# Sheet8.net
KiCad netlist of a schematic drawn in Altium Designer
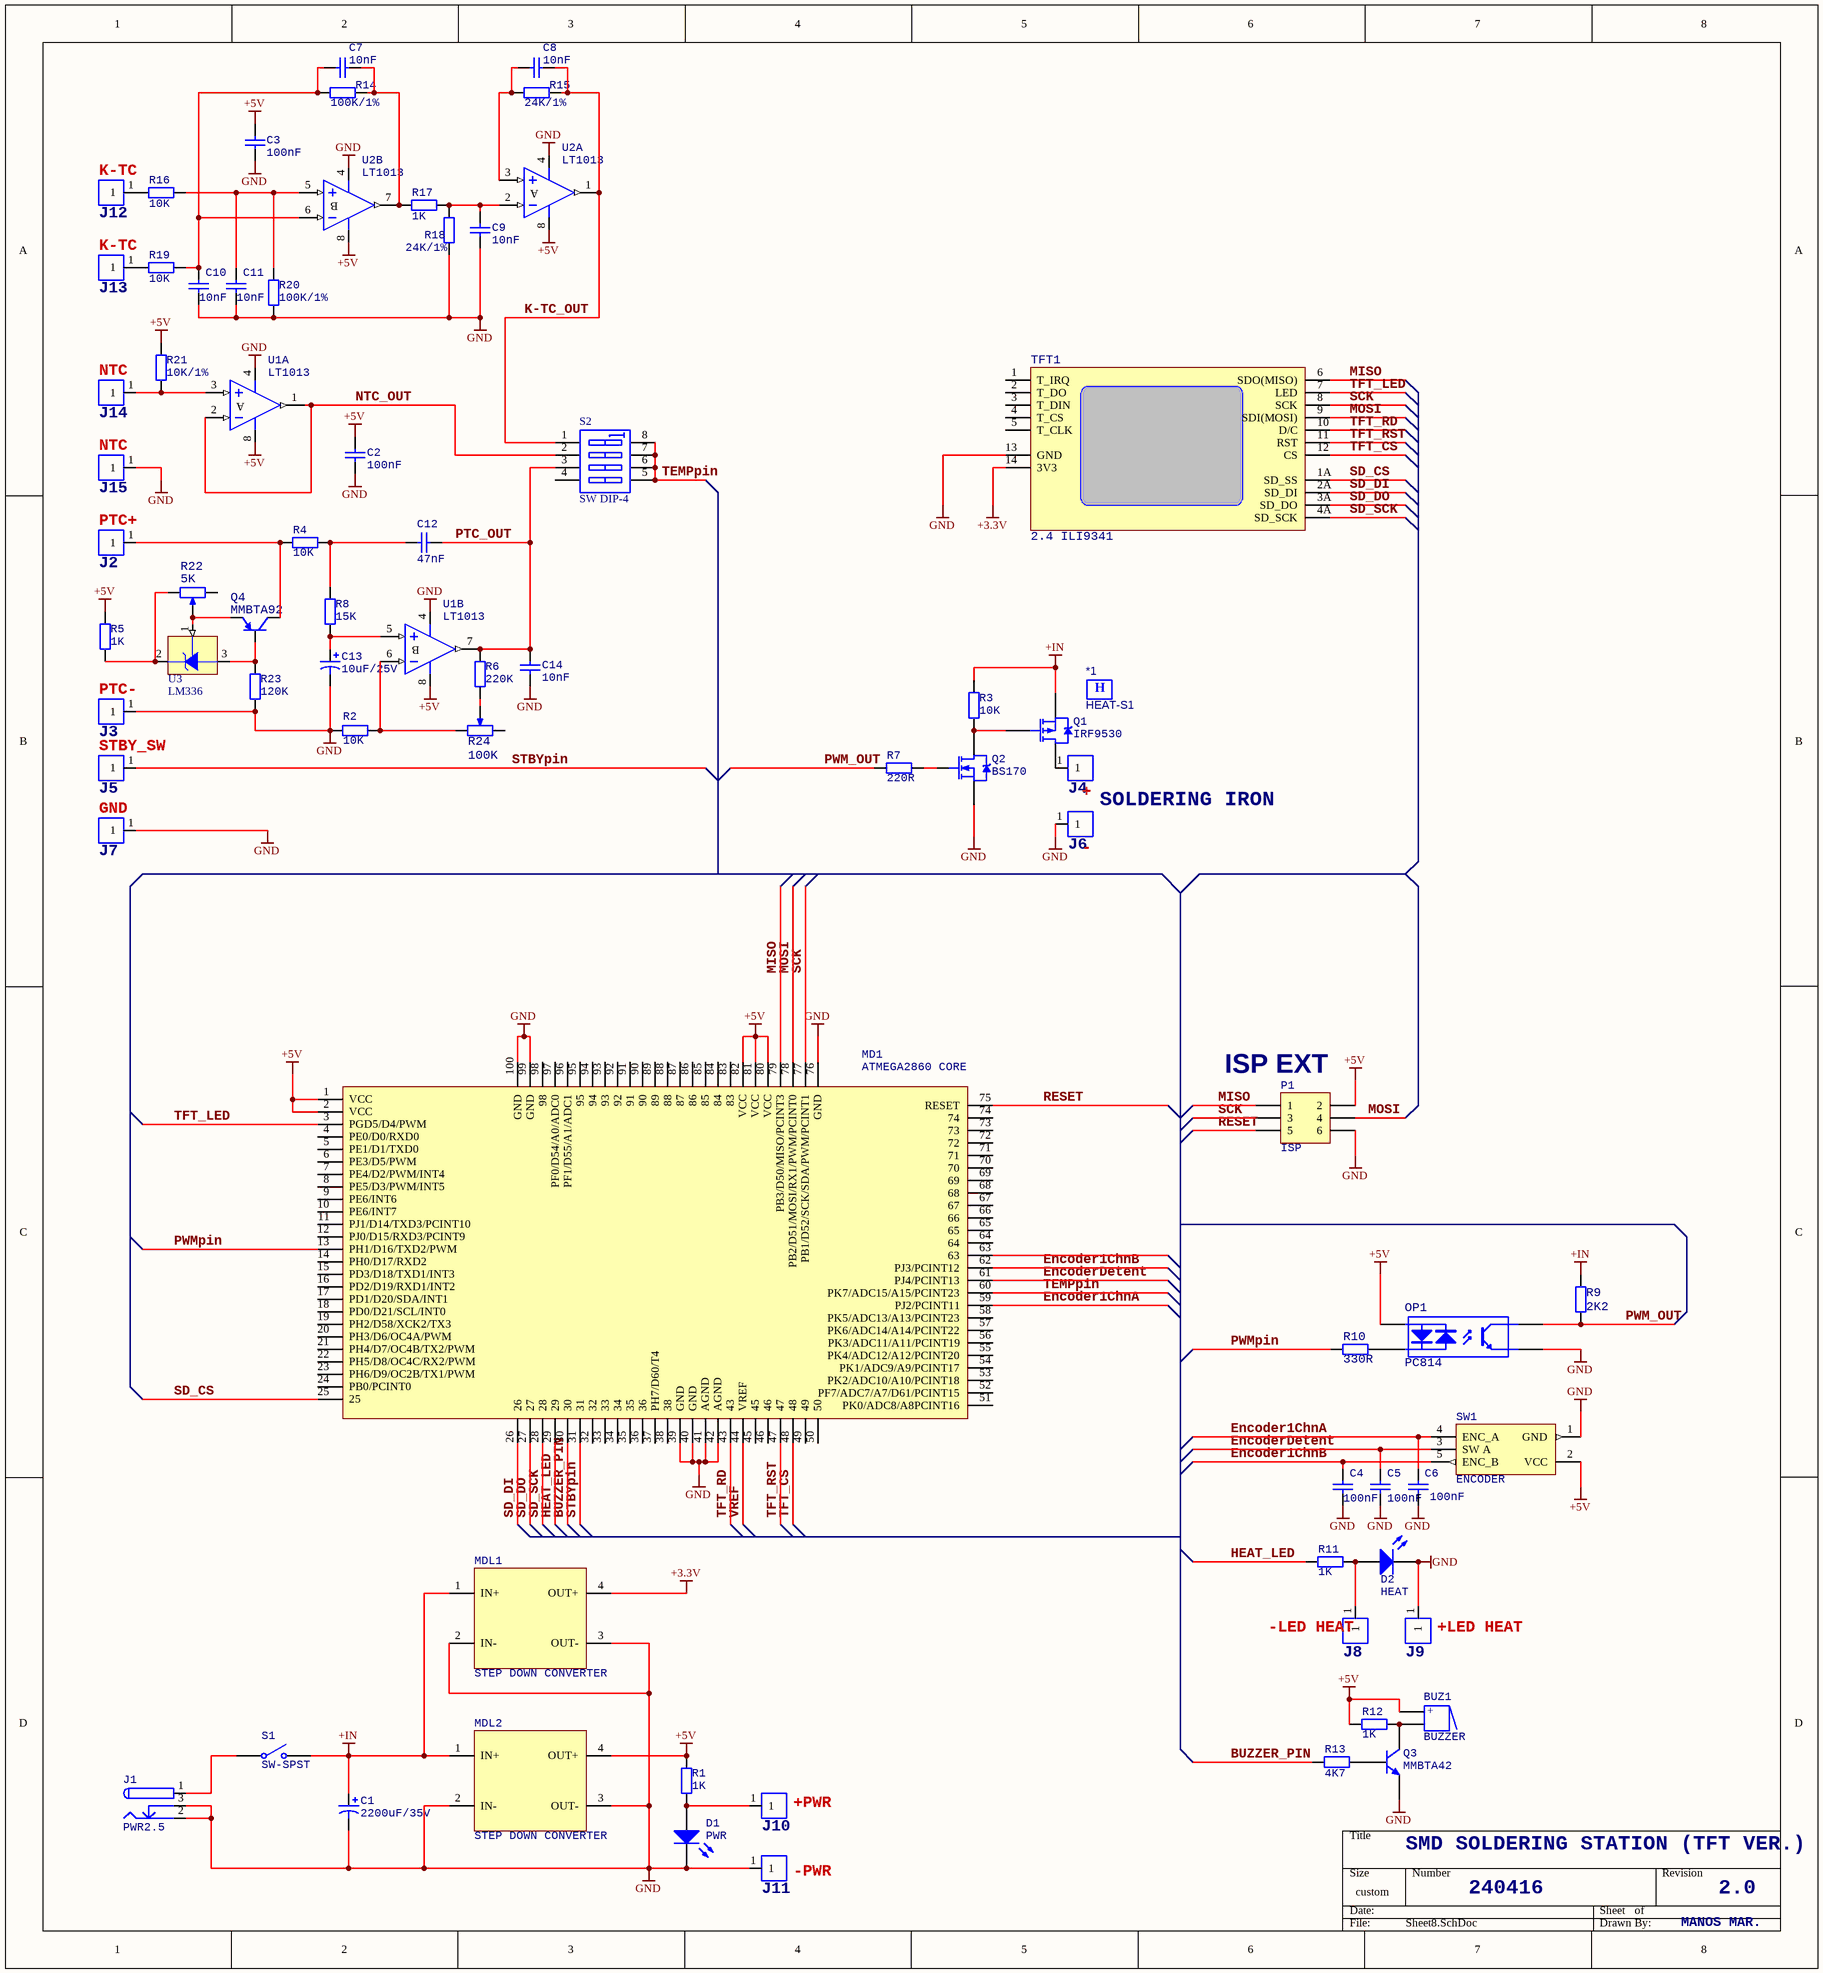
[diagram p0: Sheet8.SchDoc]

(export (version "E")
  (design (tool "Eeschema 10.0.6"))
  (components
    (comp (ref "*1")
      (value "HEAT-S1")
      (footprint "SK 104 HEATSHINK")
      (libsource (lib "SG_INTLIB") (part "HEAT-S1"))
    )
    (comp (ref "BUZ1") (value "BUZZER") (footprint "BUZZER") (libsource (lib "SMD STATION") (part "BUZZER")))
    (comp (ref "C1")
      (value "2200uF/35V")
      (footprint "RB5-10.5")
      (description "Polarized Capacitor (Radial)")
      (fields (field (name "PUBLISHER") "Altium Limited"))
      (libsource (lib "Miscellaneous Devices") (part "Cap Pol1"))
    )
    (comp (ref "C2")
      (value "100nF")
      (footprint "0805")
      (description "Capacitor, Ceramic, 4.7uF 10% 16V 0805 (2012) X7R")
      (fields (field (name "TOLERANCE") "10 %"))
      (libsource (lib "AltiumDesignLibrary") (part "CAP-NP"))
    )
    (comp (ref "C3")
      (value "100nF")
      (footprint "0805")
      (description "Capacitor, Ceramic, 4.7uF 10% 16V 0805 (2012) X7R")
      (fields (field (name "TOLERANCE") "10 %"))
      (libsource (lib "AltiumDesignLibrary") (part "CAP-NP"))
    )
    (comp (ref "C4")
      (value "100nF")
      (footprint "0805")
      (description "Capacitor")
      (fields (field (name "PUBLISHER") "Altium Limited"))
      (libsource (lib "Miscellaneous Devices") (part "Cap"))
    )
    (comp (ref "C5")
      (value "100nF")
      (footprint "0805")
      (description "Capacitor")
      (fields (field (name "PUBLISHER") "Altium Limited"))
      (libsource (lib "Miscellaneous Devices") (part "Cap"))
    )
    (comp (ref "C6")
      (value "100nF")
      (footprint "0805")
      (description "Capacitor")
      (fields (field (name "PUBLISHER") "Altium Limited"))
      (libsource (lib "Miscellaneous Devices") (part "Cap"))
    )
    (comp (ref "C7")
      (value "10nF")
      (footprint "0805")
      (description "Capacitor, Ceramic, 4.7uF 10% 16V 0805 (2012) X7R")
      (fields (field (name "TOLERANCE") "10 %"))
      (libsource (lib "AltiumDesignLibrary") (part "CAP-NP"))
    )
    (comp (ref "C8")
      (value "10nF")
      (footprint "0805")
      (description "Capacitor, Ceramic, 4.7uF 10% 16V 0805 (2012) X7R")
      (fields (field (name "TOLERANCE") "10 %"))
      (libsource (lib "AltiumDesignLibrary") (part "CAP-NP"))
    )
    (comp (ref "C9")
      (value "10nF")
      (footprint "0805")
      (description "Capacitor, Ceramic, 4.7uF 10% 16V 0805 (2012) X7R")
      (fields (field (name "TOLERANCE") "10 %"))
      (libsource (lib "AltiumDesignLibrary") (part "CAP-NP"))
    )
    (comp (ref "C10")
      (value "10nF")
      (footprint "0805")
      (description "Capacitor, Ceramic, 4.7uF 10% 16V 0805 (2012) X7R")
      (fields (field (name "TOLERANCE") "10 %"))
      (libsource (lib "AltiumDesignLibrary") (part "CAP-NP"))
    )
    (comp (ref "C11")
      (value "10nF")
      (footprint "0805")
      (description "Capacitor, Ceramic, 4.7uF 10% 16V 0805 (2012) X7R")
      (fields (field (name "TOLERANCE") "10 %"))
      (libsource (lib "AltiumDesignLibrary") (part "CAP-NP"))
    )
    (comp (ref "C12")
      (value "47nF")
      (footprint "0805")
      (description "Capacitor, Ceramic, 4.7uF 10% 16V 0805 (2012) X7R")
      (fields (field (name "TOLERANCE") "10 %"))
      (libsource (lib "AltiumDesignLibrary") (part "CAP-NP"))
    )
    (comp (ref "C13")
      (value "10uF/25V")
      (footprint "RB-08")
      (description "Polarized Capacitor (Radial)")
      (fields (field (name "PUBLISHER") "Altium Limited"))
      (libsource (lib "Miscellaneous Devices") (part "Cap Pol1"))
    )
    (comp (ref "C14")
      (value "10nF")
      (footprint "0805")
      (description "Capacitor, Ceramic, 4.7uF 10% 16V 0805 (2012) X7R")
      (fields (field (name "TOLERANCE") "10 %"))
      (libsource (lib "AltiumDesignLibrary") (part "CAP-NP"))
    )
    (comp (ref "D1")
      (value "PWR")
      (footprint "1206D")
      (description "Typical INFRARED GaAs LED")
      (fields (field (name "PUBLISHER") "Altium Limited"))
      (libsource (lib "Miscellaneous Devices") (part "LED0"))
    )
    (comp (ref "D2")
      (value "HEAT")
      (footprint "1206D")
      (description "Typical INFRARED GaAs LED")
      (fields (field (name "PUBLISHER") "Altium Limited"))
      (libsource (lib "Miscellaneous Devices") (part "LED0"))
    )
    (comp (ref "J1")
      (value "PWR2.5")
      (footprint "POWER JACK")
      (description "Low Voltage Power Supply Connector")
      (fields (field (name "PUBLISHER") "Altium Limited"))
      (libsource (lib "Miscellaneous Connectors") (part "PWR2.5"))
    )
    (comp (ref "J2")
      (value "PTC+")
      (footprint "CON2")
      (fields (field (name "MANUFACTURER") "Sta.Ge HELLAS"))
      (libsource (lib "Z_General_SCH_Library") (part "CON1_S"))
    )
    (comp (ref "J3")
      (value "PTC-")
      (footprint "CON2")
      (fields (field (name "MANUFACTURER") "Sta.Ge HELLAS"))
      (libsource (lib "Z_General_SCH_Library") (part "CON1_S"))
    )
    (comp (ref "J4")
      (value "+")
      (footprint "CON2")
      (fields (field (name "MANUFACTURER") "Sta.Ge HELLAS"))
      (libsource (lib "") (part "CON1_S_2"))
    )
    (comp (ref "J5")
      (value "STBY_SW")
      (footprint "CON2")
      (fields (field (name "MANUFACTURER") "Sta.Ge HELLAS"))
      (libsource (lib "Z_General_SCH_Library") (part "CON1_S"))
    )
    (comp (ref "J6")
      (value "-")
      (footprint "CON2")
      (fields (field (name "MANUFACTURER") "Sta.Ge HELLAS"))
      (libsource (lib "") (part "CON1_S_2"))
    )
    (comp (ref "J7")
      (value "GND")
      (footprint "CON2")
      (fields (field (name "MANUFACTURER") "Sta.Ge HELLAS"))
      (libsource (lib "Z_General_SCH_Library") (part "CON1_S"))
    )
    (comp (ref "J8")
      (value "-LED HEAT")
      (footprint "CON2")
      (fields (field (name "MANUFACTURER") "Sta.Ge HELLAS"))
      (libsource (lib "") (part "CON1_S_1"))
    )
    (comp (ref "J9")
      (value "+LED HEAT")
      (footprint "CON2")
      (fields (field (name "MANUFACTURER") "Sta.Ge HELLAS"))
      (libsource (lib "") (part "CON1_S_1"))
    )
    (comp (ref "J10")
      (value "+PWR")
      (footprint "CON2")
      (fields (field (name "MANUFACTURER") "Sta.Ge HELLAS"))
      (libsource (lib "") (part "CON1_S_2"))
    )
    (comp (ref "J11")
      (value "-PWR")
      (footprint "CON2")
      (fields (field (name "MANUFACTURER") "Sta.Ge HELLAS"))
      (libsource (lib "") (part "CON1_S_2"))
    )
    (comp (ref "J12")
      (value "K-TC")
      (footprint "CON2")
      (fields (field (name "MANUFACTURER") "Sta.Ge HELLAS"))
      (libsource (lib "Z_General_SCH_Library") (part "CON1_S"))
    )
    (comp (ref "J13")
      (value "K-TC")
      (footprint "CON2")
      (fields (field (name "MANUFACTURER") "Sta.Ge HELLAS"))
      (libsource (lib "Z_General_SCH_Library") (part "CON1_S"))
    )
    (comp (ref "J14")
      (value "NTC")
      (footprint "CON2")
      (fields (field (name "MANUFACTURER") "Sta.Ge HELLAS"))
      (libsource (lib "Z_General_SCH_Library") (part "CON1_S"))
    )
    (comp (ref "J15")
      (value "NTC")
      (footprint "CON2")
      (fields (field (name "MANUFACTURER") "Sta.Ge HELLAS"))
      (libsource (lib "Z_General_SCH_Library") (part "CON1_S"))
    )
    (comp (ref "MD1")
      (value "ATMEGA2860 CORE")
      (footprint "ATMEGA 2560 CORE")
      (libsource (lib "SMD STATION") (part "ATMEGA2560 CORE"))
    )
    (comp (ref "MDL1")
      (value "STEP DOWN CONVERTER")
      (footprint "STEP DOWN CONVERTER MINI")
      (libsource (lib "SMD STATION") (part "STEP DOWN CONVERTER"))
    )
    (comp (ref "MDL2")
      (value "STEP DOWN CONVERTER")
      (footprint "STEP DOWN CONVERTER MINI")
      (libsource (lib "SMD STATION") (part "STEP DOWN CONVERTER"))
    )
    (comp (ref "OP1")
      (value "PC814")
      (footprint "SOP-4")
      (description "AC OPTOCUPLER")
      (libsource (lib "STAGE_MP3") (part "OPTO-AC1"))
    )
    (comp (ref "P1")
      (value "ISP")
      (footprint "HDR2X3")
      (description "Header, 3-Pin, Dual row")
      (fields (field (name "PUBLISHER") "Altium Limited"))
      (libsource (lib "Miscellaneous Connectors") (part "Header 3X2"))
    )
    (comp (ref "Q1")
      (value "IRF9530")
      (footprint "TO-220V")
      (description "P-Channel Power MOSFET")
      (fields (field (name "PUBLISHER") "Altium Limited"))
      (libsource (lib "Miscellaneous Devices") (part "PMOS-2"))
    )
    (comp (ref "Q2")
      (value "BS170")
      (footprint "T0-92")
      (description "N-Channel Power MOSFET")
      (fields (field (name "PUBLISHER") "Altium Limited"))
      (libsource (lib "Miscellaneous Devices") (part "NMOS-2"))
    )
    (comp (ref "Q3")
      (value "MMBTA42")
      (footprint "SO-G3")
      (description "NPN Bipolar Transistor")
      (fields (field (name "PUBLISHER") "Altium Limited"))
      (libsource (lib "Miscellaneous Devices") (part "NPN"))
    )
    (comp (ref "Q4")
      (value "MMBTA92")
      (footprint "SO-G3")
      (description "PNP Bipolar Transistor")
      (fields (field (name "PUBLISHER") "Altium Limited"))
      (libsource (lib "Miscellaneous Devices") (part "PNP"))
    )
    (comp (ref "R1")
      (value "1K")
      (footprint "0805")
      (description "Resistor")
      (fields (field (name "PUBLISHER") "Altium Limited"))
      (libsource (lib "Miscellaneous Devices") (part "Res2"))
    )
    (comp (ref "R2")
      (value "10K")
      (footprint "0805")
      (fields
        (field (name "MANUFACTURER") "Generic Components")
        (field (name "POWER") "0,2W")
        (field (name "SGPARTNUMBER") "R001051")
        (field (name "PUBLISHER") "Altium Limited")
      )
      (libsource (lib "SG_PCB") (part "RES"))
    )
    (comp (ref "R3")
      (value "10K")
      (footprint "0805")
      (description "Resistor")
      (fields (field (name "PUBLISHER") "Altium Limited"))
      (libsource (lib "Miscellaneous Devices") (part "Res2"))
    )
    (comp (ref "R4")
      (value "10K")
      (footprint "0805")
      (fields
        (field (name "MANUFACTURER") "Generic Components")
        (field (name "POWER") "0,2W")
        (field (name "SGPARTNUMBER") "R001051")
        (field (name "PUBLISHER") "Altium Limited")
      )
      (libsource (lib "") (part "RES_3"))
    )
    (comp (ref "R5")
      (value "1K")
      (footprint "0805")
      (fields
        (field (name "MANUFACTURER") "Generic Components")
        (field (name "POWER") "0,2W")
        (field (name "SGPARTNUMBER") "R001051")
        (field (name "PUBLISHER") "Altium Limited")
      )
      (libsource (lib "") (part "RES_2"))
    )
    (comp (ref "R6")
      (value "220K")
      (footprint "0805")
      (fields
        (field (name "MANUFACTURER") "Generic Components")
        (field (name "POWER") "0,2W")
        (field (name "SGPARTNUMBER") "R001051")
        (field (name "PUBLISHER") "Altium Limited")
      )
      (libsource (lib "") (part "RES_1"))
    )
    (comp (ref "R7")
      (value "220R")
      (footprint "0805")
      (description "Resistor")
      (fields (field (name "PUBLISHER") "Altium Limited"))
      (libsource (lib "") (part "Res2_1"))
    )
    (comp (ref "R8")
      (value "15K")
      (footprint "0805")
      (fields
        (field (name "MANUFACTURER") "Generic Components")
        (field (name "POWER") "0,2W")
        (field (name "SGPARTNUMBER") "R001051")
        (field (name "PUBLISHER") "Altium Limited")
      )
      (libsource (lib "") (part "RES_1"))
    )
    (comp (ref "R9")
      (value "2K2")
      (footprint "0805")
      (fields
        (field (name "MANUFACTURER") "Generic Components")
        (field (name "POWER") "0,2W")
        (field (name "SGPARTNUMBER") "R001051")
        (field (name "PUBLISHER") "Altium Limited")
      )
      (libsource (lib "") (part "RES_1"))
    )
    (comp (ref "R10")
      (value "330R")
      (footprint "0805")
      (fields
        (field (name "MANUFACTURER") "Generic Components")
        (field (name "POWER") "0,2W")
        (field (name "SGPARTNUMBER") "R001051")
        (field (name "PUBLISHER") "Altium Limited")
      )
      (libsource (lib "SG_PCB") (part "RES"))
    )
    (comp (ref "R11")
      (value "1K")
      (footprint "0805")
      (description "Resistor")
      (fields (field (name "PUBLISHER") "Altium Limited"))
      (libsource (lib "") (part "Res2_1"))
    )
    (comp (ref "R12")
      (value "1K")
      (footprint "0805")
      (fields
        (field (name "MANUFACTURER") "Generic Components")
        (field (name "POWER") "0,2W")
        (field (name "SGPARTNUMBER") "R001051")
        (field (name "PUBLISHER") "Altium Limited")
      )
      (libsource (lib "SG_PCB") (part "RES"))
    )
    (comp (ref "R13")
      (value "4K7")
      (footprint "0805")
      (fields
        (field (name "MANUFACTURER") "Generic Components")
        (field (name "POWER") "0,2W")
        (field (name "SGPARTNUMBER") "R001051")
        (field (name "PUBLISHER") "Altium Limited")
      )
      (libsource (lib "") (part "RES_3"))
    )
    (comp (ref "R14")
      (value "100K/1%")
      (footprint "0805")
      (fields
        (field (name "MANUFACTURER") "Generic Components")
        (field (name "POWER") "0,2W")
        (field (name "SGPARTNUMBER") "R001051")
        (field (name "PUBLISHER") "Altium Limited")
      )
      (libsource (lib "SG_PCB") (part "RES"))
    )
    (comp (ref "R15")
      (value "24K/1%")
      (footprint "0805")
      (fields
        (field (name "MANUFACTURER") "Generic Components")
        (field (name "POWER") "0,2W")
        (field (name "SGPARTNUMBER") "R001051")
        (field (name "PUBLISHER") "Altium Limited")
      )
      (libsource (lib "SG_PCB") (part "RES"))
    )
    (comp (ref "R16")
      (value "10K")
      (footprint "0805")
      (fields
        (field (name "MANUFACTURER") "Generic Components")
        (field (name "POWER") "0,2W")
        (field (name "SGPARTNUMBER") "R001051")
        (field (name "PUBLISHER") "Altium Limited")
      )
      (libsource (lib "SG_PCB") (part "RES"))
    )
    (comp (ref "R17")
      (value "1K")
      (footprint "0805")
      (fields
        (field (name "MANUFACTURER") "Generic Components")
        (field (name "POWER") "0,2W")
        (field (name "SGPARTNUMBER") "R001051")
        (field (name "PUBLISHER") "Altium Limited")
      )
      (libsource (lib "SG_PCB") (part "RES"))
    )
    (comp (ref "R18")
      (value "24K/1%")
      (footprint "0805")
      (fields
        (field (name "MANUFACTURER") "Generic Components")
        (field (name "POWER") "0,2W")
        (field (name "SGPARTNUMBER") "R001051")
        (field (name "PUBLISHER") "Altium Limited")
      )
      (libsource (lib "") (part "RES_1"))
    )
    (comp (ref "R19")
      (value "10K")
      (footprint "0805")
      (fields
        (field (name "MANUFACTURER") "Generic Components")
        (field (name "POWER") "0,2W")
        (field (name "SGPARTNUMBER") "R001051")
        (field (name "PUBLISHER") "Altium Limited")
      )
      (libsource (lib "SG_PCB") (part "RES"))
    )
    (comp (ref "R20")
      (value "100K/1%")
      (footprint "0805")
      (fields
        (field (name "MANUFACTURER") "Generic Components")
        (field (name "POWER") "0,2W")
        (field (name "SGPARTNUMBER") "R001051")
        (field (name "PUBLISHER") "Altium Limited")
      )
      (libsource (lib "") (part "RES_2"))
    )
    (comp (ref "R21")
      (value "10K/1%")
      (footprint "0805")
      (fields
        (field (name "MANUFACTURER") "Generic Components")
        (field (name "POWER") "0,2W")
        (field (name "SGPARTNUMBER") "R001051")
        (field (name "PUBLISHER") "Altium Limited")
      )
      (libsource (lib "AVR SMD SOLDERING") (part "RES"))
    )
    (comp (ref "R22")
      (value "5K")
      (footprint "VR6")
      (fields
        (field (name "MANUFACTURER") "Sta.Ge HELLAS")
        (field (name "SGPARTNUMBER") "R001049")
        (field (name "PART NUMBER") "R002107")
        (field (name "PUBLISHER") "Altium Limited")
      )
      (libsource (lib "") (part "RPot2_1"))
    )
    (comp (ref "R23")
      (value "120K")
      (footprint "0805")
      (fields
        (field (name "MANUFACTURER") "Generic Components")
        (field (name "POWER") "0,2W")
        (field (name "SGPARTNUMBER") "R001051")
        (field (name "PUBLISHER") "Altium Limited")
      )
      (libsource (lib "") (part "RES_2"))
    )
    (comp (ref "R24")
      (value "100K")
      (footprint "VR6")
      (fields
        (field (name "MANUFACTURER") "Sta.Ge HELLAS")
        (field (name "SGPARTNUMBER") "R001049")
        (field (name "PART NUMBER") "R002107")
        (field (name "PUBLISHER") "Altium Limited")
      )
      (libsource (lib "SG_INTLIB") (part "RPot2"))
    )
    (comp (ref "S1")
      (value "SW-SPST")
      (footprint "SPST-2")
      (description "Single-Pole, Single-Throw Switch")
      (fields (field (name "PUBLISHER") "Altium Limited"))
      (libsource (lib "Miscellaneous Devices") (part "SW-SPST"))
    )
    (comp (ref "S2")
      (value "SW DIP-4")
      (footprint "DIP-8")
      (description "DIP Switch, 4 Position, SPST")
      (fields (field (name "PUBLISHER") "Altium Limited"))
      (libsource (lib "Miscellaneous Devices") (part "SW DIP-4"))
    )
    (comp (ref "SW1")
      (value "ENCODER")
      (footprint "HDR1X5")
      (libsource (lib "SMD STATION") (part "ROTARY ENC"))
    )
    (comp (ref "TFT1")
      (value "2.4 ILI9341")
      (footprint "Miscellaneous Connectors:HDR1X18")
      (libsource (lib "SMD STATION") (part "2.4 TFT"))
    )
    (comp (ref "U1")
      (value "LT1013")
      (footprint "DIP-8")
      (description "Dual Precision Operational Amplifier")
      (fields (field (name "PUBLISHER") "Altium Limited"))
      (libsource (lib "LT Operational Amplifier") (part "LT1013ACJ8"))
    )
    (comp (ref "U2")
      (value "LT1013")
      (footprint "DIP-8")
      (description "Dual Precision Operational Amplifier")
      (fields (field (name "PUBLISHER") "Altium Limited"))
      (libsource (lib "LT Operational Amplifier") (part "LT1013ACJ8"))
    )
    (comp (ref "U3")
      (value "LM336")
      (footprint "Z03A")
      (description "Adjustable Micropower Voltage Reference")
      (fields (field (name "PUBLISHER") "Altium Limited"))
      (libsource (lib "NSC Power Mgt Voltage Reference") (part "LM385Z"))
    )
  )
  (nets
    (net (code "1") (name "+3.3V") (class "Default")
      (node (ref "MDL1") (pin "4") (pinfunction "OUT+_4") (pintype "passive"))
      (node (ref "TFT1") (pin "14") (pinfunction "3V3_14") (pintype "passive"))
    )
    (net (code "2") (name "+5V") (class "Default")
      (node (ref "BUZ1") (pin "1") (pinfunction "1_1") (pintype "passive"))
      (node (ref "C2") (pin "2") (pinfunction "2_2") (pintype "passive"))
      (node (ref "C3") (pin "2") (pinfunction "2_2") (pintype "passive"))
      (node (ref "MD1") (pin "1") (pinfunction "VCC_1") (pintype "passive"))
      (node (ref "MD1") (pin "2") (pinfunction "VCC_2") (pintype "passive"))
      (node (ref "MD1") (pin "80") (pinfunction "VCC_80") (pintype "passive"))
      (node (ref "MD1") (pin "81") (pinfunction "VCC_81") (pintype "passive"))
      (node (ref "MD1") (pin "82") (pinfunction "VCC_82") (pintype "passive"))
      (node (ref "MDL2") (pin "4") (pinfunction "OUT+_4") (pintype "passive"))
      (node (ref "OP1") (pin "1") (pinfunction "A_1") (pintype "passive"))
      (node (ref "P1") (pin "2") (pinfunction "2_2") (pintype "passive"))
      (node (ref "R1") (pin "2") (pinfunction "2_2") (pintype "passive"))
      (node (ref "R12") (pin "2") (pinfunction "2_2") (pintype "passive"))
      (node (ref "R21") (pin "2") (pinfunction "2_2") (pintype "passive"))
      (node (ref "R5") (pin "2") (pinfunction "2_2") (pintype "passive"))
      (node (ref "SW1") (pin "2") (pinfunction "VCC_2") (pintype "passive"))
      (node (ref "U1") (pin "8") (pinfunction "V+_8") (pintype "power_in"))
      (node (ref "U2") (pin "8") (pinfunction "V+_8") (pintype "power_in"))
    )
    (net (code "3") (name "+IN") (class "Default")
      (node (ref "C1") (pin "1") (pinfunction "1_1") (pintype "passive"))
      (node (ref "MDL1") (pin "1") (pinfunction "IN+_1") (pintype "passive"))
      (node (ref "MDL2") (pin "1") (pinfunction "IN+_1") (pintype "passive"))
      (node (ref "Q1") (pin "3") (pinfunction "S_3") (pintype "passive"))
      (node (ref "R3") (pin "2") (pinfunction "2_2") (pintype "passive"))
      (node (ref "R9") (pin "1") (pinfunction "1_1") (pintype "passive"))
      (node (ref "S1") (pin "2") (pinfunction "NO_2") (pintype "passive"))
    )
    (net (code "4") (name "/BUZZER_PIN") (class "Default")
      (node (ref "MD1") (pin "30") (pinfunction "30_30") (pintype "passive"))
      (node (ref "R13") (pin "1") (pinfunction "1_1") (pintype "passive"))
    )
    (net (code "5") (name "/Encoder1ChnA") (class "Default")
      (node (ref "C6") (pin "1") (pinfunction "1_1") (pintype "passive"))
      (node (ref "MD1") (pin "59") (pinfunction "PJ2/PCINT11_59") (pintype "passive"))
      (node (ref "SW1") (pin "4") (pinfunction "ENC_A_4") (pintype "passive"))
    )
    (net (code "6") (name "/Encoder1ChnB") (class "Default")
      (node (ref "C4") (pin "1") (pinfunction "1_1") (pintype "passive"))
      (node (ref "MD1") (pin "62") (pinfunction "PJ3/PCINT12_62") (pintype "passive"))
      (node (ref "SW1") (pin "5") (pinfunction "ENC_B_5") (pintype "output"))
    )
    (net (code "7") (name "/EncoderDetent") (class "Default")
      (node (ref "C5") (pin "1") (pinfunction "1_1") (pintype "passive"))
      (node (ref "MD1") (pin "61") (pinfunction "PJ4/PCINT13_61") (pintype "passive"))
      (node (ref "SW1") (pin "3") (pinfunction "SW_A_3") (pintype "passive"))
    )
    (net (code "8") (name "/HEAT_LED") (class "Default")
      (node (ref "MD1") (pin "29") (pinfunction "29_29") (pintype "passive"))
      (node (ref "R11") (pin "1") (pinfunction "1_1") (pintype "passive"))
    )
    (net (code "9") (name "/K-TC_OUT") (class "Default")
      (node (ref "C8") (pin "1") (pinfunction "1_1") (pintype "passive"))
      (node (ref "R15") (pin "1") (pinfunction "1_1") (pintype "passive"))
      (node (ref "S2") (pin "1") (pinfunction "A1_1") (pintype "passive"))
      (node (ref "U2") (pin "1") (pinfunction "OUT_1") (pintype "output"))
    )
    (net (code "10") (name "/MISO") (class "Default")
      (node (ref "MD1") (pin "79") (pinfunction "PB3/D50/MISO/PCINT3_79") (pintype "passive"))
      (node (ref "P1") (pin "1") (pinfunction "1_1") (pintype "passive"))
      (node (ref "TFT1") (pin "6") (pinfunction "SDO(MISO)_6") (pintype "passive"))
    )
    (net (code "11") (name "/MOSI") (class "Default")
      (node (ref "MD1") (pin "78") (pinfunction "PB2/D51/MOSI/RX1/PWM/PCINT0_78") (pintype "passive"))
      (node (ref "P1") (pin "4") (pinfunction "4_4") (pintype "passive"))
      (node (ref "TFT1") (pin "9") (pinfunction "SDI(MOSI)_9") (pintype "passive"))
    )
    (net (code "12") (name "/NTC_OUT") (class "Default")
      (node (ref "S2") (pin "2") (pinfunction "A2_2") (pintype "passive"))
      (node (ref "U1") (pin "1") (pinfunction "OUT_1") (pintype "output"))
      (node (ref "U1") (pin "2") (pinfunction "IN-_2") (pintype "input"))
    )
    (net (code "13") (name "/PTC_OUT") (class "Default")
      (node (ref "C12") (pin "1") (pinfunction "1_1") (pintype "passive"))
      (node (ref "C14") (pin "2") (pinfunction "2_2") (pintype "passive"))
      (node (ref "R6") (pin "1") (pinfunction "1_1") (pintype "passive"))
      (node (ref "S2") (pin "3") (pinfunction "A3_3") (pintype "passive"))
      (node (ref "U1") (pin "7") (pinfunction "OUT_7") (pintype "output"))
    )
    (net (code "14") (name "/PWM_OUT") (class "Default")
      (node (ref "OP1") (pin "4") (pinfunction "C_4") (pintype "passive"))
      (node (ref "R7") (pin "1") (pinfunction "1_1") (pintype "passive"))
      (node (ref "R9") (pin "2") (pinfunction "2_2") (pintype "passive"))
    )
    (net (code "15") (name "/PWMpin") (class "Default")
      (node (ref "MD1") (pin "13") (pinfunction "PH1/D16/TXD2/PWM_13") (pintype "passive"))
      (node (ref "R10") (pin "2") (pinfunction "2_2") (pintype "passive"))
    )
    (net (code "16") (name "/RESET") (class "Default")
      (node (ref "MD1") (pin "75") (pinfunction "RESET_75") (pintype "passive"))
      (node (ref "P1") (pin "5") (pinfunction "5_5") (pintype "passive"))
    )
    (net (code "17") (name "/SCK") (class "Default")
      (node (ref "MD1") (pin "77") (pinfunction "PB1/D52/SCK/SDA/PWM/PCINT1_77") (pintype "passive"))
      (node (ref "P1") (pin "3") (pinfunction "3_3") (pintype "passive"))
      (node (ref "TFT1") (pin "8") (pinfunction "SCK_8") (pintype "passive"))
    )
    (net (code "18") (name "/SD_CS") (class "Default")
      (node (ref "MD1") (pin "25") (pinfunction "25_25") (pintype "passive"))
      (node (ref "TFT1") (pin "1A") (pinfunction "SD_SS_1A") (pintype "passive"))
    )
    (net (code "19") (name "/SD_DI") (class "Default")
      (node (ref "MD1") (pin "26") (pinfunction "26_26") (pintype "passive"))
      (node (ref "TFT1") (pin "2A") (pinfunction "SD_DI_2A") (pintype "passive"))
    )
    (net (code "20") (name "/SD_DO") (class "Default")
      (node (ref "MD1") (pin "27") (pinfunction "27_27") (pintype "passive"))
      (node (ref "TFT1") (pin "3A") (pinfunction "SD_DO_3A") (pintype "passive"))
    )
    (net (code "21") (name "/SD_SCK") (class "Default")
      (node (ref "MD1") (pin "28") (pinfunction "28_28") (pintype "passive"))
      (node (ref "TFT1") (pin "4A") (pinfunction "SD_SCK_4A") (pintype "passive"))
    )
    (net (code "22") (name "/STBYpin") (class "Default")
      (node (ref "J5") (pin "1") (pinfunction "1_1") (pintype "passive"))
      (node (ref "MD1") (pin "31") (pinfunction "31_31") (pintype "passive"))
    )
    (net (code "23") (name "/TEMPpin") (class "Default")
      (node (ref "MD1") (pin "60") (pinfunction "PK7/ADC15/A15/PCINT23_60") (pintype "passive"))
      (node (ref "S2") (pin "5") (pinfunction "B4_5") (pintype "passive"))
      (node (ref "S2") (pin "6") (pinfunction "B3_6") (pintype "passive"))
      (node (ref "S2") (pin "7") (pinfunction "B2_7") (pintype "passive"))
      (node (ref "S2") (pin "8") (pinfunction "B1_8") (pintype "passive"))
    )
    (net (code "24") (name "/TFT_CS") (class "Default")
      (node (ref "MD1") (pin "48") (pinfunction "48_48") (pintype "passive"))
      (node (ref "TFT1") (pin "12") (pinfunction "CS_12") (pintype "passive"))
    )
    (net (code "25") (name "/TFT_LED") (class "Default")
      (node (ref "MD1") (pin "3") (pinfunction "PGD5/D4/PWM_3") (pintype "passive"))
      (node (ref "TFT1") (pin "7") (pinfunction "LED_7") (pintype "passive"))
    )
    (net (code "26") (name "/TFT_RD") (class "Default")
      (node (ref "MD1") (pin "43") (pinfunction "43_43") (pintype "passive"))
      (node (ref "TFT1") (pin "10") (pinfunction "D/C_10") (pintype "passive"))
    )
    (net (code "27") (name "/TFT_RST") (class "Default")
      (node (ref "MD1") (pin "47") (pinfunction "47_47") (pintype "passive"))
      (node (ref "TFT1") (pin "11") (pinfunction "RST_11") (pintype "passive"))
    )
    (net (code "28") (name "/VREF") (class "Default")
      (node (ref "MD1") (pin "44") (pinfunction "VREF_44") (pintype "passive"))
    )
    (net (code "29") (name "GND") (class "Default")
      (node (ref "C1") (pin "2") (pinfunction "2_2") (pintype "passive"))
      (node (ref "C10") (pin "1") (pinfunction "1_1") (pintype "passive"))
      (node (ref "C11") (pin "1") (pinfunction "1_1") (pintype "passive"))
      (node (ref "C13") (pin "2") (pinfunction "2_2") (pintype "passive"))
      (node (ref "C14") (pin "1") (pinfunction "1_1") (pintype "passive"))
      (node (ref "C2") (pin "1") (pinfunction "1_1") (pintype "passive"))
      (node (ref "C3") (pin "1") (pinfunction "1_1") (pintype "passive"))
      (node (ref "C4") (pin "2") (pinfunction "2_2") (pintype "passive"))
      (node (ref "C5") (pin "2") (pinfunction "2_2") (pintype "passive"))
      (node (ref "C6") (pin "2") (pinfunction "2_2") (pintype "passive"))
      (node (ref "C9") (pin "2") (pinfunction "2_2") (pintype "passive"))
      (node (ref "D1") (pin "2") (pinfunction "K_2") (pintype "passive"))
      (node (ref "D2") (pin "2") (pinfunction "K_2") (pintype "passive"))
      (node (ref "J1") (pin "2") (pinfunction "2_2") (pintype "power_in"))
      (node (ref "J1") (pin "3") (pinfunction "3_3") (pintype "power_in"))
      (node (ref "J11") (pin "1") (pinfunction "1_1") (pintype "passive"))
      (node (ref "J15") (pin "1") (pinfunction "1_1") (pintype "passive"))
      (node (ref "J3") (pin "1") (pinfunction "1_1") (pintype "passive"))
      (node (ref "J6") (pin "1") (pinfunction "1_1") (pintype "passive"))
      (node (ref "J7") (pin "1") (pinfunction "1_1") (pintype "passive"))
      (node (ref "J9") (pin "1") (pinfunction "1_1") (pintype "passive"))
      (node (ref "MD1") (pin "100") (pinfunction "GND_100") (pintype "passive"))
      (node (ref "MD1") (pin "39") (pinfunction "GND_39") (pintype "passive"))
      (node (ref "MD1") (pin "40") (pinfunction "GND_40") (pintype "passive"))
      (node (ref "MD1") (pin "41") (pinfunction "AGND_41") (pintype "passive"))
      (node (ref "MD1") (pin "42") (pinfunction "AGND_42") (pintype "passive"))
      (node (ref "MD1") (pin "76") (pinfunction "GND_76") (pintype "passive"))
      (node (ref "MD1") (pin "99") (pinfunction "GND_99") (pintype "passive"))
      (node (ref "MDL1") (pin "2") (pinfunction "IN-_2") (pintype "passive"))
      (node (ref "MDL1") (pin "3") (pinfunction "OUT-_3") (pintype "passive"))
      (node (ref "MDL2") (pin "2") (pinfunction "IN-_2") (pintype "passive"))
      (node (ref "MDL2") (pin "3") (pinfunction "OUT-_3") (pintype "passive"))
      (node (ref "OP1") (pin "3") (pinfunction "E_3") (pintype "passive"))
      (node (ref "P1") (pin "6") (pinfunction "6_6") (pintype "passive"))
      (node (ref "Q2") (pin "3") (pinfunction "S_3") (pintype "passive"))
      (node (ref "Q3") (pin "2") (pinfunction "E_2") (pintype "passive"))
      (node (ref "R18") (pin "2") (pinfunction "2_2") (pintype "passive"))
      (node (ref "R2") (pin "2") (pinfunction "2_2") (pintype "passive"))
      (node (ref "R20") (pin "1") (pinfunction "1_1") (pintype "passive"))
      (node (ref "R23") (pin "1") (pinfunction "1_1") (pintype "passive"))
      (node (ref "SW1") (pin "1") (pinfunction "GND_1") (pintype "output"))
      (node (ref "TFT1") (pin "13") (pinfunction "GND_13") (pintype "passive"))
      (node (ref "U1") (pin "4") (pinfunction "V-_4") (pintype "power_in"))
      (node (ref "U2") (pin "4") (pinfunction "V-_4") (pintype "power_in"))
    )
    (net (code "30") (name "Net-(C12-Pad2)") (class "Default")
      (node (ref "C12") (pin "2") (pinfunction "2_2") (pintype "passive"))
      (node (ref "R4") (pin "2") (pinfunction "2_2") (pintype "passive"))
      (node (ref "R8") (pin "1") (pinfunction "1_1") (pintype "passive"))
    )
    (net (code "31") (name "Net-(D1-A)") (class "Default")
      (node (ref "D1") (pin "1") (pinfunction "A_1") (pintype "passive"))
      (node (ref "J10") (pin "1") (pinfunction "1_1") (pintype "passive"))
      (node (ref "R1") (pin "1") (pinfunction "1_1") (pintype "passive"))
    )
    (net (code "32") (name "Net-(D2-A)") (class "Default")
      (node (ref "D2") (pin "1") (pinfunction "A_1") (pintype "passive"))
      (node (ref "J8") (pin "1") (pinfunction "1_1") (pintype "passive"))
      (node (ref "R11") (pin "2") (pinfunction "2_2") (pintype "passive"))
    )
    (net (code "33") (name "Net-(J12-Pad1)") (class "Default")
      (node (ref "J12") (pin "1") (pinfunction "1_1") (pintype "passive"))
      (node (ref "R16") (pin "2") (pinfunction "2_2") (pintype "passive"))
    )
    (net (code "34") (name "Net-(J13-Pad1)") (class "Default")
      (node (ref "J13") (pin "1") (pinfunction "1_1") (pintype "passive"))
      (node (ref "R19") (pin "2") (pinfunction "2_2") (pintype "passive"))
    )
    (net (code "35") (name "Net-(OP1-K)") (class "Default")
      (node (ref "OP1") (pin "2") (pinfunction "K_2") (pintype "passive"))
      (node (ref "R10") (pin "1") (pinfunction "1_1") (pintype "passive"))
    )
    (net (code "36") (name "Net-(Q1-D)") (class "Default")
      (node (ref "J4") (pin "1") (pinfunction "1_1") (pintype "passive"))
      (node (ref "Q1") (pin "2") (pinfunction "D_2") (pintype "passive"))
    )
    (net (code "37") (name "Net-(Q1-G)") (class "Default")
      (node (ref "Q1") (pin "1") (pinfunction "G_1") (pintype "passive"))
      (node (ref "Q2") (pin "2") (pinfunction "D_2") (pintype "passive"))
      (node (ref "R3") (pin "1") (pinfunction "1_1") (pintype "passive"))
    )
    (net (code "38") (name "Net-(Q2-G)") (class "Default")
      (node (ref "Q2") (pin "1") (pinfunction "G_1") (pintype "passive"))
      (node (ref "R7") (pin "2") (pinfunction "2_2") (pintype "passive"))
    )
    (net (code "39") (name "Net-(Q3-B)") (class "Default")
      (node (ref "Q3") (pin "1") (pinfunction "B_1") (pintype "passive"))
      (node (ref "R13") (pin "2") (pinfunction "2_2") (pintype "passive"))
    )
    (net (code "40") (name "Net-(Q3-C)") (class "Default")
      (node (ref "BUZ1") (pin "2") (pinfunction "2_2") (pintype "passive"))
      (node (ref "Q3") (pin "3") (pinfunction "C_3") (pintype "passive"))
      (node (ref "R12") (pin "1") (pinfunction "1_1") (pintype "passive"))
    )
    (net (code "41") (name "Net-(Q4-B)") (class "Default")
      (node (ref "Q4") (pin "1") (pinfunction "B_1") (pintype "passive"))
      (node (ref "R23") (pin "2") (pinfunction "2_2") (pintype "passive"))
      (node (ref "U3") (pin "3") (pinfunction "-V_3") (pintype "passive"))
    )
    (net (code "42") (name "Net-(Q4-C)") (class "Default")
      (node (ref "J2") (pin "1") (pinfunction "1_1") (pintype "passive"))
      (node (ref "Q4") (pin "3") (pinfunction "C_3") (pintype "passive"))
      (node (ref "R4") (pin "1") (pinfunction "1_1") (pintype "passive"))
    )
    (net (code "43") (name "Net-(Q4-E)") (class "Default")
      (node (ref "Q4") (pin "2") (pinfunction "E_2") (pintype "passive"))
      (node (ref "R22") (pin "2") (pinfunction "TAP_2") (pintype "passive"))
      (node (ref "U3") (pin "1") (pinfunction "ADJ_1") (pintype "input"))
    )
    (net (code "44") (name "Net-(R22-TOP)") (class "Default")
      (node (ref "R22") (pin "1") (pinfunction "TOP_1") (pintype "passive"))
      (node (ref "R5") (pin "1") (pinfunction "1_1") (pintype "passive"))
      (node (ref "U3") (pin "2") (pinfunction "+V_2") (pintype "passive"))
    )
    (net (code "45") (name "Net-(R24-BOT)") (class "Default")
      (node (ref "R2") (pin "1") (pinfunction "1_1") (pintype "passive"))
      (node (ref "R24") (pin "1") (pinfunction "BOT_1") (pintype "passive"))
      (node (ref "U1") (pin "6") (pinfunction "IN-_6") (pintype "input"))
    )
    (net (code "46") (name "Net-(R24-TAP)") (class "Default")
      (node (ref "R24") (pin "2") (pinfunction "TAP_2") (pintype "passive"))
      (node (ref "R6") (pin "2") (pinfunction "2_2") (pintype "passive"))
    )
    (net (code "47") (name "Net-(S1-COMMON)") (class "Default")
      (node (ref "J1") (pin "1") (pinfunction "1_1") (pintype "power_in"))
      (node (ref "S1") (pin "1") (pinfunction "COMMON_1") (pintype "passive"))
    )
    (net (code "48") (name "Net-(U1A-IN+)") (class "Default")
      (node (ref "J14") (pin "1") (pinfunction "1_1") (pintype "passive"))
      (node (ref "R21") (pin "1") (pinfunction "1_1") (pintype "passive"))
      (node (ref "U1") (pin "3") (pinfunction "IN+_3") (pintype "input"))
    )
    (net (code "49") (name "Net-(U1B-IN+)") (class "Default")
      (node (ref "C13") (pin "1") (pinfunction "1_1") (pintype "passive"))
      (node (ref "R8") (pin "2") (pinfunction "2_2") (pintype "passive"))
      (node (ref "U1") (pin "5") (pinfunction "IN+_5") (pintype "input"))
    )
    (net (code "50") (name "Net-(U2A-IN+)") (class "Default")
      (node (ref "C8") (pin "2") (pinfunction "2_2") (pintype "passive"))
      (node (ref "R15") (pin "2") (pinfunction "2_2") (pintype "passive"))
      (node (ref "U2") (pin "3") (pinfunction "IN+_3") (pintype "input"))
    )
    (net (code "51") (name "Net-(U2A-IN-)") (class "Default")
      (node (ref "C9") (pin "1") (pinfunction "1_1") (pintype "passive"))
      (node (ref "R17") (pin "1") (pinfunction "1_1") (pintype "passive"))
      (node (ref "R18") (pin "1") (pinfunction "1_1") (pintype "passive"))
      (node (ref "U2") (pin "2") (pinfunction "IN-_2") (pintype "input"))
    )
    (net (code "52") (name "Net-(U2B-IN+)") (class "Default")
      (node (ref "C11") (pin "2") (pinfunction "2_2") (pintype "passive"))
      (node (ref "R16") (pin "1") (pinfunction "1_1") (pintype "passive"))
      (node (ref "R20") (pin "2") (pinfunction "2_2") (pintype "passive"))
      (node (ref "U2") (pin "5") (pinfunction "IN+_5") (pintype "input"))
    )
    (net (code "53") (name "Net-(U2B-IN-)") (class "Default")
      (node (ref "C10") (pin "2") (pinfunction "2_2") (pintype "passive"))
      (node (ref "C7") (pin "2") (pinfunction "2_2") (pintype "passive"))
      (node (ref "R14") (pin "2") (pinfunction "2_2") (pintype "passive"))
      (node (ref "R19") (pin "1") (pinfunction "1_1") (pintype "passive"))
      (node (ref "U2") (pin "6") (pinfunction "IN-_6") (pintype "input"))
    )
    (net (code "54") (name "Net-(U2B-OUT)") (class "Default")
      (node (ref "C7") (pin "1") (pinfunction "1_1") (pintype "passive"))
      (node (ref "R14") (pin "1") (pinfunction "1_1") (pintype "passive"))
      (node (ref "R17") (pin "2") (pinfunction "2_2") (pintype "passive"))
      (node (ref "U2") (pin "7") (pinfunction "OUT_7") (pintype "output"))
    )
    (net (code "55") (name "unconnected-(MD1-PB0{slash}PCINT0-Pad24)") (class "Default")
      (node (ref "MD1") (pin "24") (pinfunction "PB0/PCINT0_24") (pintype "passive"))
    )
    (net (code "56") (name "unconnected-(MD1-PD0{slash}D21{slash}SCL{slash}INT0-Pad18)") (class "Default")
      (node (ref "MD1") (pin "18") (pinfunction "PD0/D21/SCL/INT0_18") (pintype "passive"))
    )
    (net (code "57") (name "unconnected-(MD1-PD1{slash}D20{slash}SDA{slash}INT1-Pad17)") (class "Default")
      (node (ref "MD1") (pin "17") (pinfunction "PD1/D20/SDA/INT1_17") (pintype "passive"))
    )
    (net (code "58") (name "unconnected-(MD1-PD2{slash}D19{slash}RXD1{slash}INT2-Pad16)") (class "Default")
      (node (ref "MD1") (pin "16") (pinfunction "PD2/D19/RXD1/INT2_16") (pintype "passive"))
    )
    (net (code "59") (name "unconnected-(MD1-PD3{slash}D18{slash}TXD1{slash}INT3-Pad15)") (class "Default")
      (node (ref "MD1") (pin "15") (pinfunction "PD3/D18/TXD1/INT3_15") (pintype "passive"))
    )
    (net (code "60") (name "unconnected-(MD1-PE0{slash}D0{slash}RXD0-Pad4)") (class "Default")
      (node (ref "MD1") (pin "4") (pinfunction "PE0/D0/RXD0_4") (pintype "passive"))
    )
    (net (code "61") (name "unconnected-(MD1-PE1{slash}D1{slash}TXD0-Pad5)") (class "Default")
      (node (ref "MD1") (pin "5") (pinfunction "PE1/D1/TXD0_5") (pintype "passive"))
    )
    (net (code "62") (name "unconnected-(MD1-PE3{slash}D5{slash}PWM-Pad6)") (class "Default")
      (node (ref "MD1") (pin "6") (pinfunction "PE3/D5/PWM_6") (pintype "passive"))
    )
    (net (code "63") (name "unconnected-(MD1-PE4{slash}D2{slash}PWM{slash}INT4-Pad7)") (class "Default")
      (node (ref "MD1") (pin "7") (pinfunction "PE4/D2/PWM/INT4_7") (pintype "passive"))
    )
    (net (code "64") (name "unconnected-(MD1-PE5{slash}D3{slash}PWM{slash}INT5-Pad8)") (class "Default")
      (node (ref "MD1") (pin "8") (pinfunction "PE5/D3/PWM/INT5_8") (pintype "passive"))
    )
    (net (code "65") (name "unconnected-(MD1-PE6{slash}INT6-Pad9)") (class "Default")
      (node (ref "MD1") (pin "9") (pinfunction "PE6/INT6_9") (pintype "passive"))
    )
    (net (code "66") (name "unconnected-(MD1-PE6{slash}INT7-Pad10)") (class "Default")
      (node (ref "MD1") (pin "10") (pinfunction "PE6/INT7_10") (pintype "passive"))
    )
    (net (code "67") (name "unconnected-(MD1-PF0{slash}D54{slash}A0{slash}ADC0-Pad97)") (class "Default")
      (node (ref "MD1") (pin "97") (pinfunction "PF0/D54/A0/ADC0_97") (pintype "passive"))
    )
    (net (code "68") (name "unconnected-(MD1-PF1{slash}D55{slash}A1{slash}ADC1-Pad96)") (class "Default")
      (node (ref "MD1") (pin "96") (pinfunction "PF1/D55/A1/ADC1_96") (pintype "passive"))
    )
    (net (code "69") (name "unconnected-(MD1-PF7{slash}ADC7{slash}A7{slash}D61{slash}PCINT15-Pad52)") (class "Default")
      (node (ref "MD1") (pin "52") (pinfunction "PF7/ADC7/A7/D61/PCINT15_52") (pintype "passive"))
    )
    (net (code "70") (name "unconnected-(MD1-PH0{slash}D17{slash}RXD2-Pad14)") (class "Default")
      (node (ref "MD1") (pin "14") (pinfunction "PH0/D17/RXD2_14") (pintype "passive"))
    )
    (net (code "71") (name "unconnected-(MD1-PH2{slash}D58{slash}XCK2{slash}TX3-Pad19)") (class "Default")
      (node (ref "MD1") (pin "19") (pinfunction "PH2/D58/XCK2/TX3_19") (pintype "passive"))
    )
    (net (code "72") (name "unconnected-(MD1-PH3{slash}D6{slash}OC4A{slash}PWM-Pad20)") (class "Default")
      (node (ref "MD1") (pin "20") (pinfunction "PH3/D6/OC4A/PWM_20") (pintype "passive"))
    )
    (net (code "73") (name "unconnected-(MD1-PH4{slash}D7{slash}OC4B{slash}TX2{slash}PWM-Pad21)") (class "Default")
      (node (ref "MD1") (pin "21") (pinfunction "PH4/D7/OC4B/TX2/PWM_21") (pintype "passive"))
    )
    (net (code "74") (name "unconnected-(MD1-PH5{slash}D8{slash}OC4C{slash}RX2{slash}PWM-Pad22)") (class "Default")
      (node (ref "MD1") (pin "22") (pinfunction "PH5/D8/OC4C/RX2/PWM_22") (pintype "passive"))
    )
    (net (code "75") (name "unconnected-(MD1-PH6{slash}D9{slash}OC2B{slash}TX1{slash}PWM-Pad23)") (class "Default")
      (node (ref "MD1") (pin "23") (pinfunction "PH6/D9/OC2B/TX1/PWM_23") (pintype "passive"))
    )
    (net (code "76") (name "unconnected-(MD1-PH7{slash}D60{slash}T4-Pad37)") (class "Default")
      (node (ref "MD1") (pin "37") (pinfunction "PH7/D60/T4_37") (pintype "passive"))
    )
    (net (code "77") (name "unconnected-(MD1-PJ0{slash}D15{slash}RXD3{slash}PCINT9-Pad12)") (class "Default")
      (node (ref "MD1") (pin "12") (pinfunction "PJ0/D15/RXD3/PCINT9_12") (pintype "passive"))
    )
    (net (code "78") (name "unconnected-(MD1-PJ1{slash}D14{slash}TXD3{slash}PCINT10-Pad11)") (class "Default")
      (node (ref "MD1") (pin "11") (pinfunction "PJ1/D14/TXD3/PCINT10_11") (pintype "passive"))
    )
    (net (code "79") (name "unconnected-(MD1-PK0{slash}ADC8{slash}A8PCINT16-Pad51)") (class "Default")
      (node (ref "MD1") (pin "51") (pinfunction "PK0/ADC8/A8PCINT16_51") (pintype "passive"))
    )
    (net (code "80") (name "unconnected-(MD1-PK1{slash}ADC9{slash}A9{slash}PCINT17-Pad54)") (class "Default")
      (node (ref "MD1") (pin "54") (pinfunction "PK1/ADC9/A9/PCINT17_54") (pintype "passive"))
    )
    (net (code "81") (name "unconnected-(MD1-PK2{slash}ADC10{slash}A10{slash}PCINT18-Pad53)") (class "Default")
      (node (ref "MD1") (pin "53") (pinfunction "PK2/ADC10/A10/PCINT18_53") (pintype "passive"))
    )
    (net (code "82") (name "unconnected-(MD1-PK3{slash}ADC11{slash}A11{slash}PCINT19-Pad56)") (class "Default")
      (node (ref "MD1") (pin "56") (pinfunction "PK3/ADC11/A11/PCINT19_56") (pintype "passive"))
    )
    (net (code "83") (name "unconnected-(MD1-PK4{slash}ADC12{slash}A12{slash}PCINT20-Pad55)") (class "Default")
      (node (ref "MD1") (pin "55") (pinfunction "PK4/ADC12/A12/PCINT20_55") (pintype "passive"))
    )
    (net (code "84") (name "unconnected-(MD1-PK5{slash}ADC13{slash}A13{slash}PCINT23-Pad58)") (class "Default")
      (node (ref "MD1") (pin "58") (pinfunction "PK5/ADC13/A13/PCINT23_58") (pintype "passive"))
    )
    (net (code "85") (name "unconnected-(MD1-PK6{slash}ADC14{slash}A14{slash}PCINT22-Pad57)") (class "Default")
      (node (ref "MD1") (pin "57") (pinfunction "PK6/ADC14/A14/PCINT22_57") (pintype "passive"))
    )
    (net (code "86") (name "unconnected-(MD1-Pad32)") (class "Default")
      (node (ref "MD1") (pin "32") (pinfunction "32_32") (pintype "passive"))
    )
    (net (code "87") (name "unconnected-(MD1-Pad33)") (class "Default")
      (node (ref "MD1") (pin "33") (pinfunction "33_33") (pintype "passive"))
    )
    (net (code "88") (name "unconnected-(MD1-Pad34)") (class "Default")
      (node (ref "MD1") (pin "34") (pinfunction "34_34") (pintype "passive"))
    )
    (net (code "89") (name "unconnected-(MD1-Pad35)") (class "Default")
      (node (ref "MD1") (pin "35") (pinfunction "35_35") (pintype "passive"))
    )
    (net (code "90") (name "unconnected-(MD1-Pad36)") (class "Default")
      (node (ref "MD1") (pin "36") (pinfunction "36_36") (pintype "passive"))
    )
    (net (code "91") (name "unconnected-(MD1-Pad38)") (class "Default")
      (node (ref "MD1") (pin "38") (pinfunction "38_38") (pintype "passive"))
    )
    (net (code "92") (name "unconnected-(MD1-Pad45)") (class "Default")
      (node (ref "MD1") (pin "45") (pinfunction "45_45") (pintype "passive"))
    )
    (net (code "93") (name "unconnected-(MD1-Pad46)") (class "Default")
      (node (ref "MD1") (pin "46") (pinfunction "46_46") (pintype "passive"))
    )
    (net (code "94") (name "unconnected-(MD1-Pad49)") (class "Default")
      (node (ref "MD1") (pin "49") (pinfunction "49_49") (pintype "passive"))
    )
    (net (code "95") (name "unconnected-(MD1-Pad50)") (class "Default")
      (node (ref "MD1") (pin "50") (pinfunction "50_50") (pintype "passive"))
    )
    (net (code "96") (name "unconnected-(MD1-Pad63)") (class "Default")
      (node (ref "MD1") (pin "63") (pinfunction "63_63") (pintype "passive"))
    )
    (net (code "97") (name "unconnected-(MD1-Pad64)") (class "Default")
      (node (ref "MD1") (pin "64") (pinfunction "64_64") (pintype "passive"))
    )
    (net (code "98") (name "unconnected-(MD1-Pad65)") (class "Default")
      (node (ref "MD1") (pin "65") (pinfunction "65_65") (pintype "passive"))
    )
    (net (code "99") (name "unconnected-(MD1-Pad66)") (class "Default")
      (node (ref "MD1") (pin "66") (pinfunction "66_66") (pintype "passive"))
    )
    (net (code "100") (name "unconnected-(MD1-Pad67)") (class "Default")
      (node (ref "MD1") (pin "67") (pinfunction "67_67") (pintype "passive"))
    )
    (net (code "101") (name "unconnected-(MD1-Pad68)") (class "Default")
      (node (ref "MD1") (pin "68") (pinfunction "68_68") (pintype "passive"))
    )
    (net (code "102") (name "unconnected-(MD1-Pad69)") (class "Default")
      (node (ref "MD1") (pin "69") (pinfunction "69_69") (pintype "passive"))
    )
    (net (code "103") (name "unconnected-(MD1-Pad70)") (class "Default")
      (node (ref "MD1") (pin "70") (pinfunction "70_70") (pintype "passive"))
    )
    (net (code "104") (name "unconnected-(MD1-Pad71)") (class "Default")
      (node (ref "MD1") (pin "71") (pinfunction "71_71") (pintype "passive"))
    )
    (net (code "105") (name "unconnected-(MD1-Pad72)") (class "Default")
      (node (ref "MD1") (pin "72") (pinfunction "72_72") (pintype "passive"))
    )
    (net (code "106") (name "unconnected-(MD1-Pad73)") (class "Default")
      (node (ref "MD1") (pin "73") (pinfunction "73_73") (pintype "passive"))
    )
    (net (code "107") (name "unconnected-(MD1-Pad74)") (class "Default")
      (node (ref "MD1") (pin "74") (pinfunction "74_74") (pintype "passive"))
    )
    (net (code "108") (name "unconnected-(MD1-Pad83)") (class "Default")
      (node (ref "MD1") (pin "83") (pinfunction "83_83") (pintype "passive"))
    )
    (net (code "109") (name "unconnected-(MD1-Pad84)") (class "Default")
      (node (ref "MD1") (pin "84") (pinfunction "84_84") (pintype "passive"))
    )
    (net (code "110") (name "unconnected-(MD1-Pad85)") (class "Default")
      (node (ref "MD1") (pin "85") (pinfunction "85_85") (pintype "passive"))
    )
    (net (code "111") (name "unconnected-(MD1-Pad86)") (class "Default")
      (node (ref "MD1") (pin "86") (pinfunction "86_86") (pintype "passive"))
    )
    (net (code "112") (name "unconnected-(MD1-Pad87)") (class "Default")
      (node (ref "MD1") (pin "87") (pinfunction "87_87") (pintype "passive"))
    )
    (net (code "113") (name "unconnected-(MD1-Pad88)") (class "Default")
      (node (ref "MD1") (pin "88") (pinfunction "88_88") (pintype "passive"))
    )
    (net (code "114") (name "unconnected-(MD1-Pad89)") (class "Default")
      (node (ref "MD1") (pin "89") (pinfunction "89_89") (pintype "passive"))
    )
    (net (code "115") (name "unconnected-(MD1-Pad90)") (class "Default")
      (node (ref "MD1") (pin "90") (pinfunction "90_90") (pintype "passive"))
    )
    (net (code "116") (name "unconnected-(MD1-Pad91)") (class "Default")
      (node (ref "MD1") (pin "91") (pinfunction "91_91") (pintype "passive"))
    )
    (net (code "117") (name "unconnected-(MD1-Pad92)") (class "Default")
      (node (ref "MD1") (pin "92") (pinfunction "92_92") (pintype "passive"))
    )
    (net (code "118") (name "unconnected-(MD1-Pad93)") (class "Default")
      (node (ref "MD1") (pin "93") (pinfunction "93_93") (pintype "passive"))
    )
    (net (code "119") (name "unconnected-(MD1-Pad94)") (class "Default")
      (node (ref "MD1") (pin "94") (pinfunction "94_94") (pintype "passive"))
    )
    (net (code "120") (name "unconnected-(MD1-Pad95)") (class "Default")
      (node (ref "MD1") (pin "95") (pinfunction "95_95") (pintype "passive"))
    )
    (net (code "121") (name "unconnected-(MD1-Pad98)") (class "Default")
      (node (ref "MD1") (pin "98") (pinfunction "98_98") (pintype "passive"))
    )
    (net (code "122") (name "unconnected-(R22-BOT-Pad3)") (class "Default")
      (node (ref "R22") (pin "3") (pinfunction "BOT_3") (pintype "passive"))
    )
    (net (code "123") (name "unconnected-(R24-TOP-Pad3)") (class "Default")
      (node (ref "R24") (pin "3") (pinfunction "TOP_3") (pintype "passive"))
    )
    (net (code "124") (name "unconnected-(S2-A4-Pad4)") (class "Default")
      (node (ref "S2") (pin "4") (pinfunction "A4_4") (pintype "passive"))
    )
    (net (code "125") (name "unconnected-(TFT1-T_CLK-Pad5)") (class "Default")
      (node (ref "TFT1") (pin "5") (pinfunction "T_CLK_5") (pintype "passive"))
    )
    (net (code "126") (name "unconnected-(TFT1-T_CS-Pad4)") (class "Default")
      (node (ref "TFT1") (pin "4") (pinfunction "T_CS_4") (pintype "passive"))
    )
    (net (code "127") (name "unconnected-(TFT1-T_DIN-Pad3)") (class "Default")
      (node (ref "TFT1") (pin "3") (pinfunction "T_DIN_3") (pintype "passive"))
    )
    (net (code "128") (name "unconnected-(TFT1-T_DO-Pad2)") (class "Default")
      (node (ref "TFT1") (pin "2") (pinfunction "T_DO_2") (pintype "passive"))
    )
    (net (code "129") (name "unconnected-(TFT1-T_IRQ-Pad1)") (class "Default")
      (node (ref "TFT1") (pin "1") (pinfunction "T_IRQ_1") (pintype "passive"))
    )
  )
)
